# 02_egitim_robotu.net
KiCad netlist of a schematic drawn in EAGLE
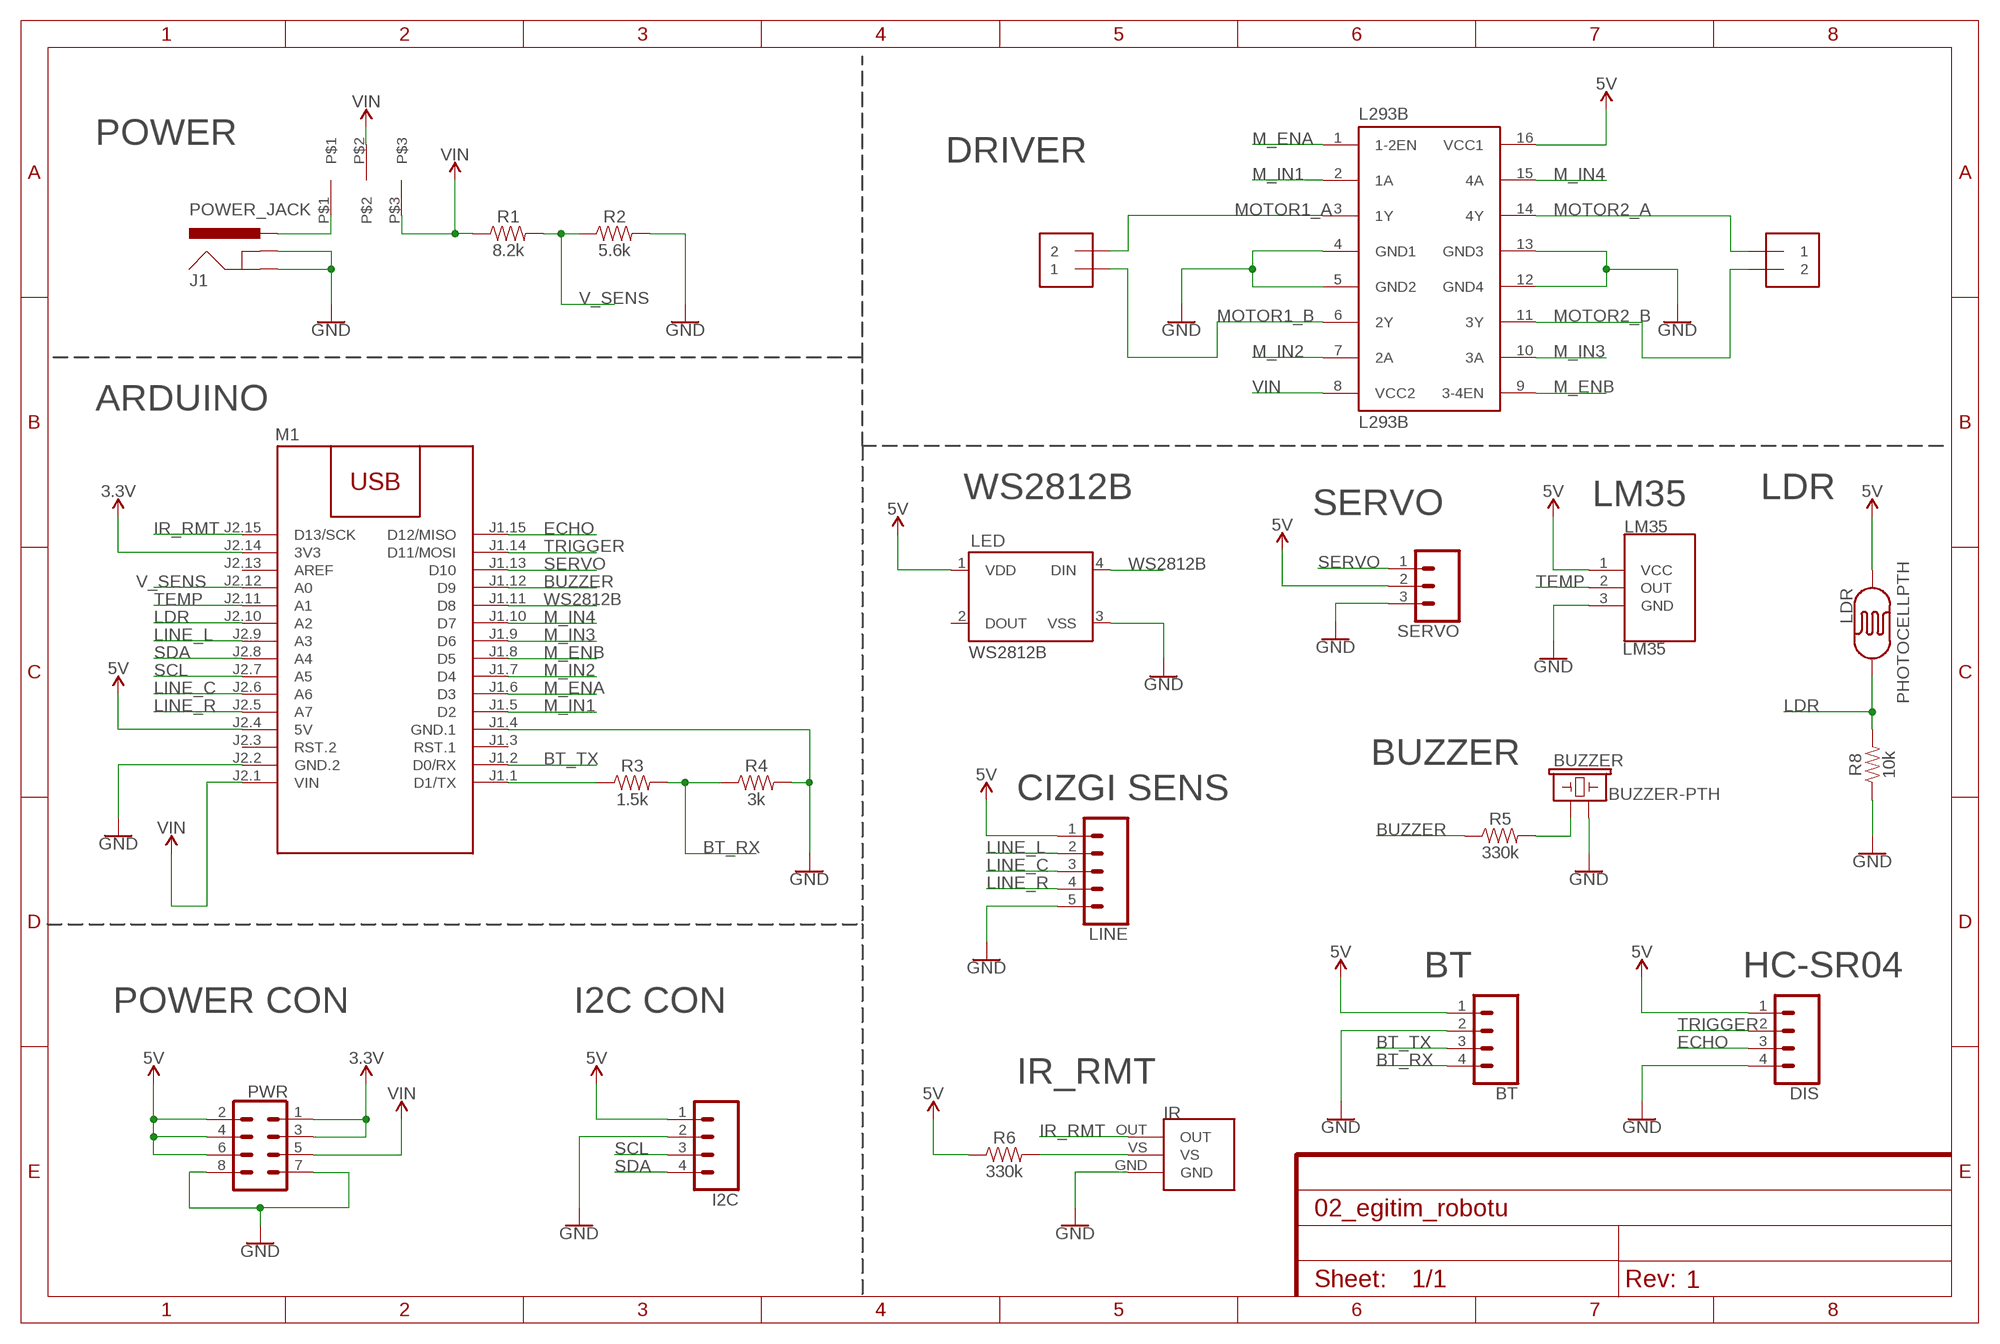
[diagram p0: schematic, sheet 1]

(export (version "E")
  (design (tool "Eeschema 10.0.6"))
  (components
    (comp (ref "BT")
      (value "CONN_04")
      (footprint "eagle-import:1X04")
      (libsource (lib "eagle-import") (part "CONN_04"))
    )
    (comp (ref "BUZZER")
      (value "BUZZER-PTH")
      (footprint "eagle-import:BUZZER-12MM")
      (libsource (lib "eagle-import") (part "BUZZER-PTH"))
    )
    (comp (ref "DIS")
      (value "CONN_04")
      (footprint "eagle-import:1X04")
      (libsource (lib "eagle-import") (part "CONN_04"))
    )
    (comp (ref "I2C")
      (value "CONN_04")
      (footprint "eagle-import:1X04")
      (libsource (lib "eagle-import") (part "CONN_04"))
    )
    (comp (ref "IR")
      (value "TSOP2238THT")
      (footprint "eagle-import:TSOP2238")
      (libsource (lib "eagle-import") (part "TSOP2238THT"))
    )
    (comp (ref "J1")
      (value "POWER_JACK")
      (footprint "eagle-import:POWER_JACK_PTH")
      (libsource (lib "eagle-import") (part "POWER_JACK"))
    )
    (comp (ref "L293B")
      (value "L293B")
      (footprint "eagle-import:DIL16")
      (fields (field (name "MPN") "L293D"))
      (libsource (lib "eagle-import") (part "L293D"))
    )
    (comp (ref "LDR")
      (value "PHOTOCELLPTH")
      (footprint "eagle-import:PHOTOCELL")
      (libsource (lib "eagle-import") (part "PHOTOCELLPTH"))
    )
    (comp (ref "LED")
      (value "WS2812B")
      (footprint "eagle-import:WS2812B")
      (libsource (lib "eagle-import") (part "WS2812B"))
    )
    (comp (ref "LINE")
      (value "CONN_05")
      (footprint "eagle-import:1X05")
      (libsource (lib "eagle-import") (part "CONN_05"))
    )
    (comp (ref "LM35")
      (value "LM35")
      (footprint "eagle-import:TO-92")
      (libsource (lib "eagle-import") (part "LM35"))
    )
    (comp (ref "M1")
      (value "ARDUINO-NANO")
      (footprint "eagle-import:ARDUINO-NANO")
      (libsource (lib "eagle-import") (part "ARDUINO-NANO"))
    )
    (comp (ref "MPW1")
      (value "1X2-3.5MM")
      (footprint "eagle-import:1X2-3.5MM")
      (libsource (lib "eagle-import") (part "1X2-3.5MM"))
    )
    (comp (ref "MPW2")
      (value "1X2-3.5MM")
      (footprint "eagle-import:1X2-3.5MM")
      (libsource (lib "eagle-import") (part "1X2-3.5MM"))
    )
    (comp (ref "PWR")
      (value "CONN_04X2")
      (footprint "eagle-import:2X4")
      (libsource (lib "eagle-import") (part "CONN_04X2"))
    )
    (comp (ref "R1")
      (value "8.2k")
      (footprint "eagle-import:AXIAL-0.3")
      (libsource (lib "eagle-import") (part "1KOHM-HORIZ-1/4W-5%"))
    )
    (comp (ref "R2")
      (value "5.6k")
      (footprint "eagle-import:AXIAL-0.3")
      (libsource (lib "eagle-import") (part "1KOHM-HORIZ-1/4W-5%"))
    )
    (comp (ref "R3")
      (value "1.5k")
      (footprint "eagle-import:AXIAL-0.3")
      (libsource (lib "eagle-import") (part "1KOHM-HORIZ-1/4W-5%"))
    )
    (comp (ref "R4")
      (value "3k")
      (footprint "eagle-import:AXIAL-0.3")
      (libsource (lib "eagle-import") (part "1KOHM-HORIZ-1/4W-5%"))
    )
    (comp (ref "R5")
      (value "330k")
      (footprint "eagle-import:AXIAL-0.3")
      (libsource (lib "eagle-import") (part "1KOHM-HORIZ-1/4W-5%"))
    )
    (comp (ref "R6")
      (value "330k")
      (footprint "eagle-import:AXIAL-0.3")
      (libsource (lib "eagle-import") (part "1KOHM-HORIZ-1/4W-5%"))
    )
    (comp (ref "R8")
      (value "10k")
      (footprint "eagle-import:AXIAL-0.3")
      (libsource (lib "eagle-import") (part "1KOHM-HORIZ-1/4W-5%"))
    )
    (comp (ref "SERVO")
      (value "CONN_03")
      (footprint "eagle-import:1X03")
      (libsource (lib "eagle-import") (part "CONN_03"))
    )
    (comp (ref "SW1")
      (value "SURGULU_SIVIC")
      (footprint "eagle-import:SURGULU_SIVIC")
      (libsource (lib "eagle-import") (part "SURGULU_SIVIC"))
    )
  )
  (nets
    (net (code "1") (name "/BT_RX") (class "Default")
      (node (ref "BT") (pin "4") (pinfunction "4_4") (pintype "passive"))
      (node (ref "R3") (pin "P$2") (pinfunction "2_P$2") (pintype "passive"))
      (node (ref "R4") (pin "P$1") (pinfunction "1_P$1") (pintype "passive"))
    )
    (net (code "2") (name "/BT_TX") (class "Default")
      (node (ref "BT") (pin "3") (pinfunction "3_3") (pintype "passive"))
      (node (ref "M1") (pin "J1.2") (pinfunction "D0/RX_J1.2") (pintype "bidirectional"))
    )
    (net (code "3") (name "/BUZZER") (class "Default")
      (node (ref "M1") (pin "J1.12") (pinfunction "D9_J1.12") (pintype "bidirectional"))
      (node (ref "R5") (pin "P$1") (pinfunction "1_P$1") (pintype "passive"))
    )
    (net (code "4") (name "/ECHO") (class "Default")
      (node (ref "DIS") (pin "3") (pinfunction "3_3") (pintype "passive"))
      (node (ref "M1") (pin "J1.15") (pinfunction "D12/MISO_J1.15") (pintype "bidirectional"))
    )
    (net (code "5") (name "/IR_RMT") (class "Default")
      (node (ref "IR") (pin "OUT") (pinfunction "OUT_OUT") (pintype "output"))
      (node (ref "M1") (pin "J2.15") (pinfunction "D13/SCK_J2.15") (pintype "bidirectional"))
    )
    (net (code "6") (name "/LDR") (class "Default")
      (node (ref "LDR") (pin "2") (pinfunction "P$2_2") (pintype "bidirectional"))
      (node (ref "M1") (pin "J2.10") (pinfunction "A2_J2.10") (pintype "bidirectional"))
      (node (ref "R8") (pin "P$2") (pinfunction "2_P$2") (pintype "passive"))
    )
    (net (code "7") (name "/LINE_C") (class "Default")
      (node (ref "LINE") (pin "3") (pinfunction "3_3") (pintype "passive"))
      (node (ref "M1") (pin "J2.6") (pinfunction "A6_J2.6") (pintype "bidirectional"))
    )
    (net (code "8") (name "/LINE_L") (class "Default")
      (node (ref "LINE") (pin "2") (pinfunction "2_2") (pintype "passive"))
      (node (ref "M1") (pin "J2.9") (pinfunction "A3_J2.9") (pintype "bidirectional"))
    )
    (net (code "9") (name "/LINE_R") (class "Default")
      (node (ref "LINE") (pin "4") (pinfunction "4_4") (pintype "passive"))
      (node (ref "M1") (pin "J2.5") (pinfunction "A7_J2.5") (pintype "bidirectional"))
    )
    (net (code "10") (name "/MOTOR1_A") (class "Default")
      (node (ref "L293B") (pin "3") (pinfunction "1Y_3") (pintype "output"))
      (node (ref "MPW1") (pin "2") (pinfunction "2_2") (pintype "passive"))
    )
    (net (code "11") (name "/MOTOR1_B") (class "Default")
      (node (ref "L293B") (pin "6") (pinfunction "2Y_6") (pintype "output"))
      (node (ref "MPW1") (pin "1") (pinfunction "1_1") (pintype "passive"))
    )
    (net (code "12") (name "/MOTOR2_A") (class "Default")
      (node (ref "L293B") (pin "14") (pinfunction "4Y_14") (pintype "output"))
      (node (ref "MPW2") (pin "1") (pinfunction "1_1") (pintype "passive"))
    )
    (net (code "13") (name "/MOTOR2_B") (class "Default")
      (node (ref "L293B") (pin "11") (pinfunction "3Y_11") (pintype "output"))
      (node (ref "MPW2") (pin "2") (pinfunction "2_2") (pintype "passive"))
    )
    (net (code "14") (name "/M_ENA") (class "Default")
      (node (ref "L293B") (pin "1") (pinfunction "1-2EN_1") (pintype "input"))
      (node (ref "M1") (pin "J1.6") (pinfunction "D3_J1.6") (pintype "bidirectional"))
    )
    (net (code "15") (name "/M_ENB") (class "Default")
      (node (ref "L293B") (pin "9") (pinfunction "3-4EN_9") (pintype "input"))
      (node (ref "M1") (pin "J1.8") (pinfunction "D5_J1.8") (pintype "bidirectional"))
    )
    (net (code "16") (name "/M_IN1") (class "Default")
      (node (ref "L293B") (pin "2") (pinfunction "1A_2") (pintype "input"))
      (node (ref "M1") (pin "J1.5") (pinfunction "D2_J1.5") (pintype "bidirectional"))
    )
    (net (code "17") (name "/M_IN2") (class "Default")
      (node (ref "L293B") (pin "7") (pinfunction "2A_7") (pintype "input"))
      (node (ref "M1") (pin "J1.7") (pinfunction "D4_J1.7") (pintype "bidirectional"))
    )
    (net (code "18") (name "/M_IN3") (class "Default")
      (node (ref "L293B") (pin "10") (pinfunction "3A_10") (pintype "input"))
      (node (ref "M1") (pin "J1.9") (pinfunction "D6_J1.9") (pintype "bidirectional"))
    )
    (net (code "19") (name "/M_IN4") (class "Default")
      (node (ref "L293B") (pin "15") (pinfunction "4A_15") (pintype "input"))
      (node (ref "M1") (pin "J1.10") (pinfunction "D7_J1.10") (pintype "bidirectional"))
    )
    (net (code "20") (name "/SCL") (class "Default")
      (node (ref "I2C") (pin "3") (pinfunction "3_3") (pintype "passive"))
      (node (ref "M1") (pin "J2.7") (pinfunction "A5_J2.7") (pintype "bidirectional"))
    )
    (net (code "21") (name "/SDA") (class "Default")
      (node (ref "I2C") (pin "4") (pinfunction "4_4") (pintype "passive"))
      (node (ref "M1") (pin "J2.8") (pinfunction "A4_J2.8") (pintype "bidirectional"))
    )
    (net (code "22") (name "/SERVO") (class "Default")
      (node (ref "M1") (pin "J1.13") (pinfunction "D10_J1.13") (pintype "bidirectional"))
      (node (ref "SERVO") (pin "1") (pinfunction "1_1") (pintype "passive"))
    )
    (net (code "23") (name "/TEMP") (class "Default")
      (node (ref "LM35") (pin "2") (pinfunction "OUT_2") (pintype "bidirectional"))
      (node (ref "M1") (pin "J2.11") (pinfunction "A1_J2.11") (pintype "bidirectional"))
    )
    (net (code "24") (name "/TRIGGER") (class "Default")
      (node (ref "DIS") (pin "2") (pinfunction "2_2") (pintype "passive"))
      (node (ref "M1") (pin "J1.14") (pinfunction "D11/MOSI_J1.14") (pintype "bidirectional"))
    )
    (net (code "25") (name "/V_SENS") (class "Default")
      (node (ref "M1") (pin "J2.12") (pinfunction "A0_J2.12") (pintype "bidirectional"))
      (node (ref "R1") (pin "P$2") (pinfunction "2_P$2") (pintype "passive"))
      (node (ref "R2") (pin "P$1") (pinfunction "1_P$1") (pintype "passive"))
    )
    (net (code "26") (name "/WS2812B") (class "Default")
      (node (ref "LED") (pin "4") (pinfunction "DIN_4") (pintype "input"))
      (node (ref "M1") (pin "J1.11") (pinfunction "D8_J1.11") (pintype "bidirectional"))
    )
    (net (code "27") (name "3.3V") (class "Default")
      (node (ref "M1") (pin "J2.14") (pinfunction "3V3_J2.14") (pintype "power_in"))
      (node (ref "PWR") (pin "1") (pinfunction "1_1") (pintype "passive"))
      (node (ref "PWR") (pin "3") (pinfunction "3_3") (pintype "passive"))
    )
    (net (code "28") (name "5V") (class "Default")
      (node (ref "BT") (pin "1") (pinfunction "1_1") (pintype "passive"))
      (node (ref "DIS") (pin "1") (pinfunction "1_1") (pintype "passive"))
      (node (ref "I2C") (pin "1") (pinfunction "1_1") (pintype "passive"))
      (node (ref "L293B") (pin "16") (pinfunction "VCC1_16") (pintype "power_in"))
      (node (ref "LDR") (pin "1") (pinfunction "P$1_1") (pintype "bidirectional"))
      (node (ref "LED") (pin "1") (pinfunction "VDD_1") (pintype "power_in"))
      (node (ref "LINE") (pin "1") (pinfunction "1_1") (pintype "passive"))
      (node (ref "LM35") (pin "1") (pinfunction "VCC_1") (pintype "bidirectional"))
      (node (ref "M1") (pin "J2.4") (pinfunction "5V_J2.4") (pintype "power_in"))
      (node (ref "PWR") (pin "2") (pinfunction "2_2") (pintype "passive"))
      (node (ref "PWR") (pin "4") (pinfunction "4_4") (pintype "passive"))
      (node (ref "PWR") (pin "6") (pinfunction "6_6") (pintype "passive"))
      (node (ref "R6") (pin "P$1") (pinfunction "1_P$1") (pintype "passive"))
      (node (ref "SERVO") (pin "2") (pinfunction "2_2") (pintype "passive"))
    )
    (net (code "29") (name "GND") (class "Default")
      (node (ref "BT") (pin "2") (pinfunction "2_2") (pintype "passive"))
      (node (ref "BUZZER") (pin "-") (pinfunction "2_-") (pintype "passive"))
      (node (ref "DIS") (pin "4") (pinfunction "4_4") (pintype "passive"))
      (node (ref "I2C") (pin "2") (pinfunction "2_2") (pintype "passive"))
      (node (ref "IR") (pin "GND") (pinfunction "GND_GND") (pintype "power_in"))
      (node (ref "J1") (pin "GND") (pinfunction "GND_GND") (pintype "bidirectional"))
      (node (ref "J1") (pin "GNDBREAK") (pinfunction "GNDBREAK_GNDBREAK") (pintype "bidirectional"))
      (node (ref "L293B") (pin "12") (pinfunction "GND4_12") (pintype "power_in"))
      (node (ref "L293B") (pin "13") (pinfunction "GND3_13") (pintype "power_in"))
      (node (ref "L293B") (pin "4") (pinfunction "GND1_4") (pintype "power_in"))
      (node (ref "L293B") (pin "5") (pinfunction "GND2_5") (pintype "power_in"))
      (node (ref "LED") (pin "3") (pinfunction "VSS_3") (pintype "power_in"))
      (node (ref "LINE") (pin "5") (pinfunction "5_5") (pintype "passive"))
      (node (ref "LM35") (pin "3") (pinfunction "GND_3") (pintype "bidirectional"))
      (node (ref "M1") (pin "J1.4") (pinfunction "GND.1_J1.4") (pintype "power_in"))
      (node (ref "M1") (pin "J2.2") (pinfunction "GND.2_J2.2") (pintype "power_in"))
      (node (ref "PWR") (pin "7") (pinfunction "7_7") (pintype "passive"))
      (node (ref "PWR") (pin "8") (pinfunction "8_8") (pintype "passive"))
      (node (ref "R2") (pin "P$2") (pinfunction "2_P$2") (pintype "passive"))
      (node (ref "R4") (pin "P$2") (pinfunction "2_P$2") (pintype "passive"))
      (node (ref "R8") (pin "P$1") (pinfunction "1_P$1") (pintype "passive"))
      (node (ref "SERVO") (pin "3") (pinfunction "3_3") (pintype "passive"))
    )
    (net (code "30") (name "Net-(BUZZER-1)") (class "Default")
      (node (ref "BUZZER") (pin "+") (pinfunction "1_+") (pintype "passive"))
      (node (ref "R5") (pin "P$2") (pinfunction "2_P$2") (pintype "passive"))
    )
    (net (code "31") (name "Net-(J1-PadPWR)") (class "Default")
      (node (ref "J1") (pin "PWR") (pinfunction "PWR_PWR") (pintype "bidirectional"))
      (node (ref "SW1") (pin "P$1") (pinfunction "P$1_P$1") (pintype "bidirectional"))
    )
    (net (code "32") (name "Net-(M1-D1{slash}TX)") (class "Default")
      (node (ref "M1") (pin "J1.1") (pinfunction "D1/TX_J1.1") (pintype "bidirectional"))
      (node (ref "R3") (pin "P$1") (pinfunction "1_P$1") (pintype "passive"))
    )
    (net (code "33") (name "Net-(R6-2)") (class "Default")
      (node (ref "IR") (pin "VS") (pinfunction "VS_VS") (pintype "power_in"))
      (node (ref "R6") (pin "P$2") (pinfunction "2_P$2") (pintype "passive"))
    )
    (net (code "34") (name "VIN") (class "Default")
      (node (ref "L293B") (pin "8") (pinfunction "VCC2_8") (pintype "power_in"))
      (node (ref "M1") (pin "J2.1") (pinfunction "VIN_J2.1") (pintype "power_in"))
      (node (ref "PWR") (pin "5") (pinfunction "5_5") (pintype "passive"))
      (node (ref "R1") (pin "P$1") (pinfunction "1_P$1") (pintype "passive"))
      (node (ref "SW1") (pin "P$2") (pinfunction "P$2_P$2") (pintype "bidirectional"))
      (node (ref "SW1") (pin "P$3") (pinfunction "P$3_P$3") (pintype "bidirectional"))
    )
    (net (code "35") (name "unconnected-(LED-DOUT-Pad2)") (class "Default")
      (node (ref "LED") (pin "2") (pinfunction "DOUT_2") (pintype "output"))
    )
    (net (code "36") (name "unconnected-(M1-AREF-PadJ2.13)") (class "Default")
      (node (ref "M1") (pin "J2.13") (pinfunction "AREF_J2.13") (pintype "bidirectional"))
    )
    (net (code "37") (name "unconnected-(M1-RST.1-PadJ1.3)") (class "Default")
      (node (ref "M1") (pin "J1.3") (pinfunction "RST.1_J1.3") (pintype "bidirectional"))
    )
    (net (code "38") (name "unconnected-(M1-RST.2-PadJ2.3)") (class "Default")
      (node (ref "M1") (pin "J2.3") (pinfunction "RST.2_J2.3") (pintype "bidirectional"))
    )
  )
)
